# RobotCtrl_Base_Func.net
KiCad netlist of a schematic drawn in Altium Designer
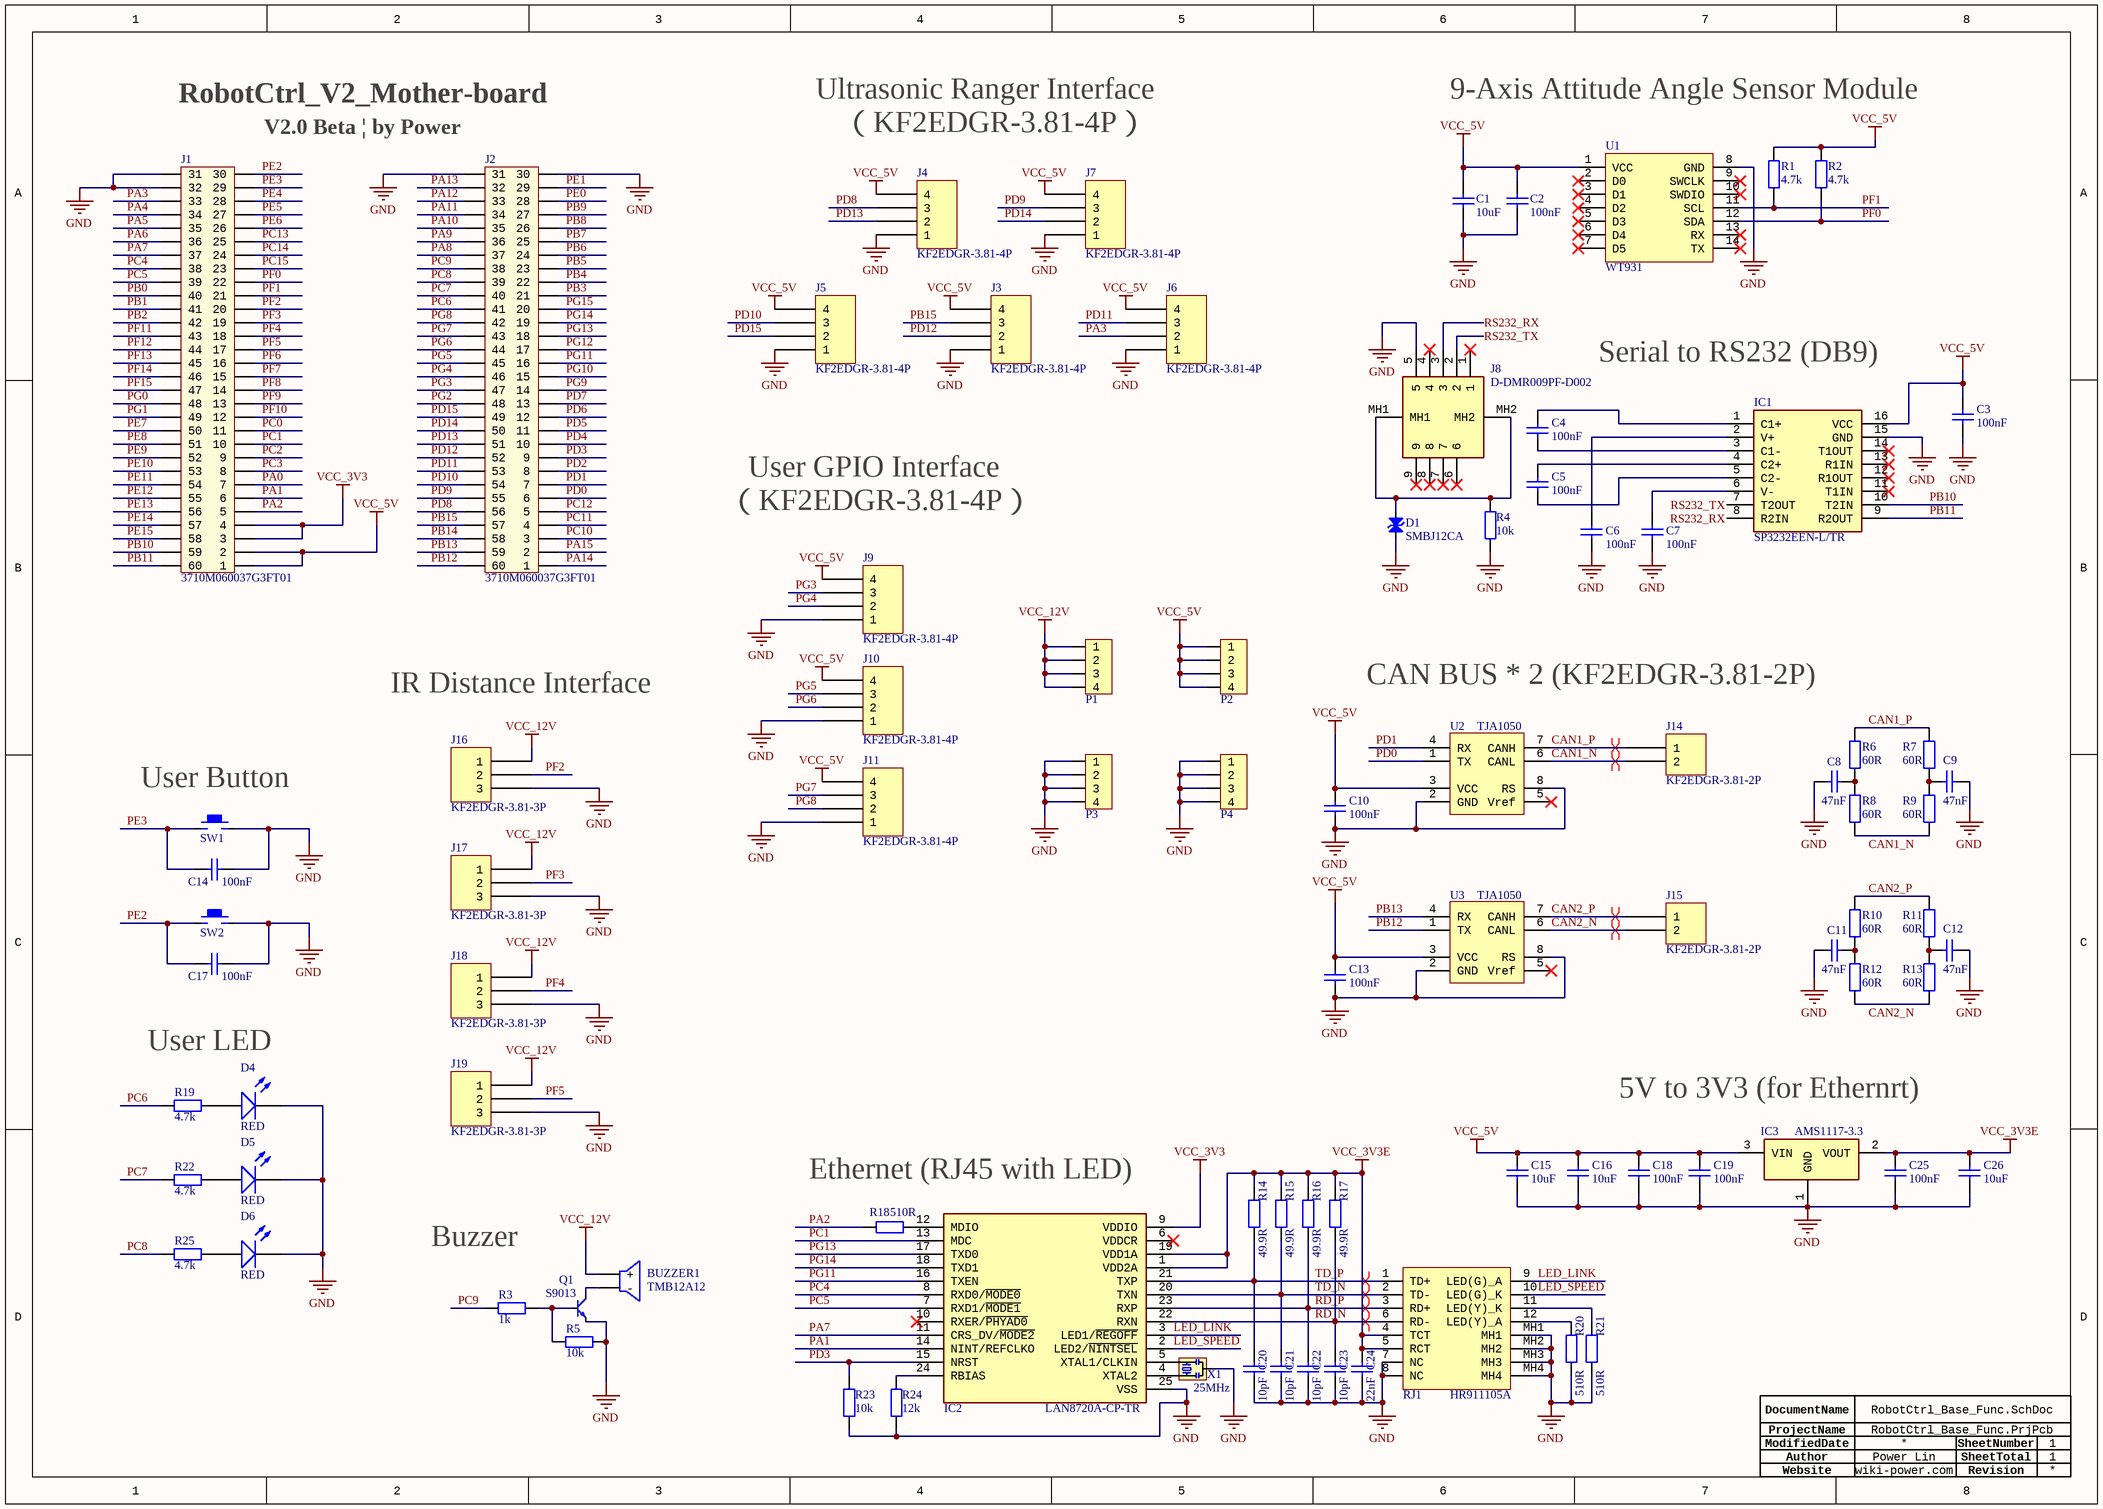
[diagram p0: RobotCtrl_Base_Func.SchDoc]

(export (version "E")
  (design (tool "Eeschema 10.0.6"))
  (components
    (comp (ref "BUZZER1")
      (value "TMB12A12")
      (footprint "DIP,P=7.6mm")
      (description "TMB12A12 有源蜂鸣器")
      (libsource (lib "Power_Lib_Altium") (part "BUZZER"))
    )
    (comp (ref "C1")
      (value "10uF")
      (footprint "CAP-0603")
      (description "贴片电容")
      (libsource (lib "Power_Lib_Altium") (part "CAP"))
    )
    (comp (ref "C2")
      (value "100nF")
      (footprint "CAP-0603")
      (description "贴片电容")
      (libsource (lib "Power_Lib_Altium") (part "CAP"))
    )
    (comp (ref "C3")
      (value "100nF")
      (footprint "CAP-0603")
      (description "贴片电容")
      (libsource (lib "Power_Lib_Altium") (part "CAP"))
    )
    (comp (ref "C4")
      (value "100nF")
      (footprint "CAP-0603")
      (description "贴片电容")
      (libsource (lib "Power_Lib_Altium") (part "CAP"))
    )
    (comp (ref "C5")
      (value "100nF")
      (footprint "CAP-0603")
      (description "贴片电容")
      (libsource (lib "Power_Lib_Altium") (part "CAP"))
    )
    (comp (ref "C6")
      (value "100nF")
      (footprint "CAP-0603")
      (description "贴片电容")
      (libsource (lib "Power_Lib_Altium") (part "CAP"))
    )
    (comp (ref "C7")
      (value "100nF")
      (footprint "CAP-0603")
      (description "贴片电容")
      (libsource (lib "Power_Lib_Altium") (part "CAP"))
    )
    (comp (ref "C8")
      (value "47nF")
      (footprint "CAP-0603")
      (description "贴片电容")
      (libsource (lib "Power_Lib_Altium") (part "CAP"))
    )
    (comp (ref "C9")
      (value "47nF")
      (footprint "CAP-0603")
      (description "贴片电容")
      (libsource (lib "Power_Lib_Altium") (part "CAP"))
    )
    (comp (ref "C10")
      (value "100nF")
      (footprint "CAP-0603")
      (description "贴片电容")
      (libsource (lib "Power_Lib_Altium") (part "CAP"))
    )
    (comp (ref "C11")
      (value "47nF")
      (footprint "CAP-0603")
      (description "贴片电容")
      (libsource (lib "Power_Lib_Altium") (part "CAP"))
    )
    (comp (ref "C12")
      (value "47nF")
      (footprint "CAP-0603")
      (description "贴片电容")
      (libsource (lib "Power_Lib_Altium") (part "CAP"))
    )
    (comp (ref "C13")
      (value "100nF")
      (footprint "CAP-0603")
      (description "贴片电容")
      (libsource (lib "Power_Lib_Altium") (part "CAP"))
    )
    (comp (ref "C14")
      (value "100nF")
      (footprint "CAP-0603")
      (description "贴片电容")
      (libsource (lib "Power_Lib_Altium") (part "CAP"))
    )
    (comp (ref "C15")
      (value "10uF")
      (footprint "CAP-0603")
      (description "贴片电容")
      (libsource (lib "Power_Lib_Altium") (part "CAP"))
    )
    (comp (ref "C16")
      (value "10uF")
      (footprint "CAP-0603")
      (description "贴片电容")
      (libsource (lib "Power_Lib_Altium") (part "CAP"))
    )
    (comp (ref "C17")
      (value "100nF")
      (footprint "CAP-0603")
      (description "贴片电容")
      (libsource (lib "Power_Lib_Altium") (part "CAP"))
    )
    (comp (ref "C18")
      (value "100nF")
      (footprint "CAP-0603")
      (description "贴片电容")
      (libsource (lib "Power_Lib_Altium") (part "CAP"))
    )
    (comp (ref "C19")
      (value "100nF")
      (footprint "CAP-0603")
      (description "贴片电容")
      (libsource (lib "Power_Lib_Altium") (part "CAP"))
    )
    (comp (ref "C20")
      (value "10pF")
      (footprint "CAP-0603")
      (description "贴片电容")
      (libsource (lib "Power_Lib_Altium") (part "CAP"))
    )
    (comp (ref "C21")
      (value "10pF")
      (footprint "CAP-0603")
      (description "贴片电容")
      (libsource (lib "Power_Lib_Altium") (part "CAP"))
    )
    (comp (ref "C22")
      (value "10pF")
      (footprint "CAP-0603")
      (description "贴片电容")
      (libsource (lib "Power_Lib_Altium") (part "CAP"))
    )
    (comp (ref "C23")
      (value "10pF")
      (footprint "CAP-0603")
      (description "贴片电容")
      (libsource (lib "Power_Lib_Altium") (part "CAP"))
    )
    (comp (ref "C24")
      (value "22nF")
      (footprint "CAP-0603")
      (description "贴片电容")
      (libsource (lib "Power_Lib_Altium") (part "CAP"))
    )
    (comp (ref "C25")
      (value "100nF")
      (footprint "CAP-0603")
      (description "贴片电容")
      (libsource (lib "Power_Lib_Altium") (part "CAP"))
    )
    (comp (ref "C26")
      (value "10uF")
      (footprint "CAP-0603")
      (description "贴片电容")
      (libsource (lib "Power_Lib_Altium") (part "CAP"))
    )
    (comp (ref "D1")
      (value "SMBJ12CA")
      (footprint "DO-214AA/SMB")
      (libsource (lib "Power_Lib_Altium") (part "TVS_C"))
    )
    (comp (ref "D4")
      (value "RED")
      (footprint "LED-0603")
      (description "发光二极管")
      (libsource (lib "Power_Lib_Altium") (part "LED"))
    )
    (comp (ref "D5")
      (value "RED")
      (footprint "LED-0603")
      (description "发光二极管")
      (libsource (lib "Power_Lib_Altium") (part "LED"))
    )
    (comp (ref "D6")
      (value "RED")
      (footprint "LED-0603")
      (description "发光二极管")
      (libsource (lib "Power_Lib_Altium") (part "LED"))
    )
    (comp (ref "IC1")
      (value "SP3232EEN-L/TR")
      (footprint "SOIC-16_150mil")
      (description "RS232 芯片")
      (fields (field (name "MOUSER PART NUMBER") "701-SP3232EEN-L/TR"))
      (libsource (lib "Power_Lib_Altium") (part "SP3232EEN"))
    )
    (comp (ref "IC2")
      (value "LAN8720A-CP-TR")
      (footprint "QFN-24-4x4")
      (description "Integrated Circuit")
      (fields (field (name "MOUSER PART NUMBER") "886-LAN8720A-CP-TR"))
      (libsource (lib "Power_Lib_Altium") (part "LAN8720A-CP-TR"))
    )
    (comp (ref "IC3")
      (value "AMS1117-3.3")
      (footprint "SOT-223")
      (description "AMS1117-3.3 1.0A")
      (fields (field (name "MANUFACTURER_PART_NUMBER") "SI2302DS") (field (name "RS PART NUMBER") "7983053P"))
      (libsource (lib "Power_Lib_Altium") (part "AMS1117"))
    )
    (comp (ref "J1")
      (value "3710M060037G3FT01")
      (footprint "3710M060037G3FT01")
      (description "B2B Connector")
      (libsource (lib "Power_Lib_Altium") (part "3710M/F"))
    )
    (comp (ref "J2")
      (value "3710M060037G3FT01")
      (footprint "3710M060037G3FT01")
      (description "B2B Connector")
      (libsource (lib "Power_Lib_Altium") (part "3710M/F"))
    )
    (comp (ref "J3")
      (value "KF2EDGR-3.81-4P")
      (footprint "FCI 06-381-4PIN")
      (description "TERM BLOCK HDR 4POS 90DEG 3.81MM")
      (fields (field (name "PART NUMBER") "OQ0432510000G") (field (name "MANUFACTURER") "Amphenol Anytek"))
      (libsource (lib "Power_Lib_Altium") (part "KF2EDGR-3.81-4P"))
    )
    (comp (ref "J4")
      (value "KF2EDGR-3.81-4P")
      (footprint "FCI 06-381-4PIN")
      (description "TERM BLOCK HDR 4POS 90DEG 3.81MM")
      (fields (field (name "PART NUMBER") "OQ0432510000G") (field (name "MANUFACTURER") "Amphenol Anytek"))
      (libsource (lib "Power_Lib_Altium") (part "KF2EDGR-3.81-4P"))
    )
    (comp (ref "J5")
      (value "KF2EDGR-3.81-4P")
      (footprint "FCI 06-381-4PIN")
      (description "TERM BLOCK HDR 4POS 90DEG 3.81MM")
      (fields (field (name "PART NUMBER") "OQ0432510000G") (field (name "MANUFACTURER") "Amphenol Anytek"))
      (libsource (lib "Power_Lib_Altium") (part "KF2EDGR-3.81-4P"))
    )
    (comp (ref "J6")
      (value "KF2EDGR-3.81-4P")
      (footprint "FCI 06-381-4PIN")
      (description "TERM BLOCK HDR 4POS 90DEG 3.81MM")
      (fields (field (name "PART NUMBER") "OQ0432510000G") (field (name "MANUFACTURER") "Amphenol Anytek"))
      (libsource (lib "Power_Lib_Altium") (part "KF2EDGR-3.81-4P"))
    )
    (comp (ref "J7")
      (value "KF2EDGR-3.81-4P")
      (footprint "FCI 06-381-4PIN")
      (description "TERM BLOCK HDR 4POS 90DEG 3.81MM")
      (fields (field (name "PART NUMBER") "OQ0432510000G") (field (name "MANUFACTURER") "Amphenol Anytek"))
      (libsource (lib "Power_Lib_Altium") (part "KF2EDGR-3.81-4P"))
    )
    (comp (ref "J8")
      (value "D-DMR009PF-D002")
      (footprint "Through Hole,P=2.77mm")
      (description "D-Sub 连接器")
      (fields
        (field (name "MANUFACTURER_PART_NUMBER") "5747844-5")
        (field (name "MOUSER PART NUMBER") "571-5747844-5")
      )
      (libsource (lib "Power_Lib_Altium") (part "DB9"))
    )
    (comp (ref "J9")
      (value "KF2EDGR-3.81-4P")
      (footprint "FCI 06-381-4PIN")
      (description "TERM BLOCK HDR 4POS 90DEG 3.81MM")
      (fields (field (name "PART NUMBER") "OQ0432510000G") (field (name "MANUFACTURER") "Amphenol Anytek"))
      (libsource (lib "Power_Lib_Altium") (part "KF2EDGR-3.81-4P"))
    )
    (comp (ref "J10")
      (value "KF2EDGR-3.81-4P")
      (footprint "FCI 06-381-4PIN")
      (description "TERM BLOCK HDR 4POS 90DEG 3.81MM")
      (fields (field (name "PART NUMBER") "OQ0432510000G") (field (name "MANUFACTURER") "Amphenol Anytek"))
      (libsource (lib "Power_Lib_Altium") (part "KF2EDGR-3.81-4P"))
    )
    (comp (ref "J11")
      (value "KF2EDGR-3.81-4P")
      (footprint "FCI 06-381-4PIN")
      (description "TERM BLOCK HDR 4POS 90DEG 3.81MM")
      (fields (field (name "PART NUMBER") "OQ0432510000G") (field (name "MANUFACTURER") "Amphenol Anytek"))
      (libsource (lib "Power_Lib_Altium") (part "KF2EDGR-3.81-4P"))
    )
    (comp (ref "J14")
      (value "KF2EDGR-3.81-2P")
      (footprint "FCI 06-381-2PIN")
      (description "TERM BLOCK HDR 2POS 90DEG 3.81MM")
      (fields (field (name "PART NUMBER") "OQ0232510000G") (field (name "MANUFACTURER") "Amphenol Anytek"))
      (libsource (lib "Power_Lib_Altium") (part "KF2EDGR-3.81-2P"))
    )
    (comp (ref "J15")
      (value "KF2EDGR-3.81-2P")
      (footprint "FCI 06-381-2PIN")
      (description "TERM BLOCK HDR 2POS 90DEG 3.81MM")
      (fields (field (name "PART NUMBER") "OQ0232510000G") (field (name "MANUFACTURER") "Amphenol Anytek"))
      (libsource (lib "Power_Lib_Altium") (part "KF2EDGR-3.81-2P"))
    )
    (comp (ref "J16")
      (value "KF2EDGR-3.81-3P")
      (footprint "FCI 06-381-3PIN")
      (description "TERM BLOCK HDR 3POS 90DEG 3.81MM")
      (fields (field (name "MANUFACTURER") "Amphenol Anytek") (field (name "PART NUMBER") "OQ0332510000G"))
      (libsource (lib "Power_Lib_Altium") (part "KF2EDGR-3.81-3P"))
    )
    (comp (ref "J17")
      (value "KF2EDGR-3.81-3P")
      (footprint "FCI 06-381-3PIN")
      (description "TERM BLOCK HDR 3POS 90DEG 3.81MM")
      (fields (field (name "MANUFACTURER") "Amphenol Anytek") (field (name "PART NUMBER") "OQ0332510000G"))
      (libsource (lib "Power_Lib_Altium") (part "KF2EDGR-3.81-3P"))
    )
    (comp (ref "J18")
      (value "KF2EDGR-3.81-3P")
      (footprint "FCI 06-381-3PIN")
      (description "TERM BLOCK HDR 3POS 90DEG 3.81MM")
      (fields (field (name "MANUFACTURER") "Amphenol Anytek") (field (name "PART NUMBER") "OQ0332510000G"))
      (libsource (lib "Power_Lib_Altium") (part "KF2EDGR-3.81-3P"))
    )
    (comp (ref "J19")
      (value "KF2EDGR-3.81-3P")
      (footprint "FCI 06-381-3PIN")
      (description "TERM BLOCK HDR 3POS 90DEG 3.81MM")
      (fields (field (name "MANUFACTURER") "Amphenol Anytek") (field (name "PART NUMBER") "OQ0332510000G"))
      (libsource (lib "Power_Lib_Altium") (part "KF2EDGR-3.81-3P"))
    )
    (comp (ref "P1")
      (value "HDR1x4_2.54")
      (footprint "HDR1X4_2.54")
      (description "Header")
      (libsource (lib "Power_Lib_Altium") (part "HDR1x4_2.54"))
    )
    (comp (ref "P2")
      (value "HDR1x4_2.54")
      (footprint "HDR1X4_2.54")
      (description "Header")
      (libsource (lib "Power_Lib_Altium") (part "HDR1x4_2.54"))
    )
    (comp (ref "P3")
      (value "HDR1x4_2.54")
      (footprint "HDR1X4_2.54")
      (description "Header")
      (libsource (lib "Power_Lib_Altium") (part "HDR1x4_2.54"))
    )
    (comp (ref "P4")
      (value "HDR1x4_2.54")
      (footprint "HDR1X4_2.54")
      (description "Header")
      (libsource (lib "Power_Lib_Altium") (part "HDR1x4_2.54"))
    )
    (comp (ref "Q1")
      (value "S9013")
      (footprint "SOT-23-3")
      (libsource (lib "Power_Lib_Altium") (part "BJT_NPN"))
    )
    (comp (ref "R1")
      (value "4.7k")
      (footprint "R-0603")
      (description "贴片电阻")
      (libsource (lib "Power_Lib_Altium") (part "RES"))
    )
    (comp (ref "R2")
      (value "4.7k")
      (footprint "R-0603")
      (description "贴片电阻")
      (libsource (lib "Power_Lib_Altium") (part "RES"))
    )
    (comp (ref "R3")
      (value "1k")
      (footprint "R-0603")
      (description "贴片电阻")
      (libsource (lib "") (part "RES_3"))
    )
    (comp (ref "R4")
      (value "10k")
      (footprint "R-0603")
      (description "贴片电阻")
      (libsource (lib "Power_Lib_Altium") (part "RES"))
    )
    (comp (ref "R5")
      (value "10k")
      (footprint "R-0603")
      (description "贴片电阻")
      (libsource (lib "") (part "RES_2"))
    )
    (comp (ref "R6")
      (value "60R")
      (footprint "R-0603")
      (description "贴片电阻")
      (libsource (lib "") (part "RES_1"))
    )
    (comp (ref "R7")
      (value "60R")
      (footprint "R-0603")
      (description "贴片电阻")
      (libsource (lib "Power_Lib_Altium") (part "RES"))
    )
    (comp (ref "R8")
      (value "60R")
      (footprint "R-0603")
      (description "贴片电阻")
      (libsource (lib "") (part "RES_1"))
    )
    (comp (ref "R9")
      (value "60R")
      (footprint "R-0603")
      (description "贴片电阻")
      (libsource (lib "Power_Lib_Altium") (part "RES"))
    )
    (comp (ref "R10")
      (value "60R")
      (footprint "R-0603")
      (description "贴片电阻")
      (libsource (lib "") (part "RES_1"))
    )
    (comp (ref "R11")
      (value "60R")
      (footprint "R-0603")
      (description "贴片电阻")
      (libsource (lib "Power_Lib_Altium") (part "RES"))
    )
    (comp (ref "R12")
      (value "60R")
      (footprint "R-0603")
      (description "贴片电阻")
      (libsource (lib "") (part "RES_1"))
    )
    (comp (ref "R13")
      (value "60R")
      (footprint "R-0603")
      (description "贴片电阻")
      (libsource (lib "Power_Lib_Altium") (part "RES"))
    )
    (comp (ref "R14")
      (value "49.9R")
      (footprint "R-0603")
      (description "贴片电阻")
      (libsource (lib "Power_Lib_Altium") (part "RES"))
    )
    (comp (ref "R15")
      (value "49.9R")
      (footprint "R-0603")
      (description "贴片电阻")
      (libsource (lib "Power_Lib_Altium") (part "RES"))
    )
    (comp (ref "R16")
      (value "49.9R")
      (footprint "R-0603")
      (description "贴片电阻")
      (libsource (lib "Power_Lib_Altium") (part "RES"))
    )
    (comp (ref "R17")
      (value "49.9R")
      (footprint "R-0603")
      (description "贴片电阻")
      (libsource (lib "Power_Lib_Altium") (part "RES"))
    )
    (comp (ref "R18")
      (value "510R")
      (footprint "R-0603")
      (description "贴片电阻")
      (libsource (lib "") (part "RES_2"))
    )
    (comp (ref "R19")
      (value "4.7k")
      (footprint "R-0603")
      (description "贴片电阻")
      (libsource (lib "") (part "RES_2"))
    )
    (comp (ref "R20")
      (value "510R")
      (footprint "R-0603")
      (description "贴片电阻")
      (libsource (lib "Power_Lib_Altium") (part "RES"))
    )
    (comp (ref "R21")
      (value "510R")
      (footprint "R-0603")
      (description "贴片电阻")
      (libsource (lib "Power_Lib_Altium") (part "RES"))
    )
    (comp (ref "R22")
      (value "4.7k")
      (footprint "R-0603")
      (description "贴片电阻")
      (libsource (lib "") (part "RES_2"))
    )
    (comp (ref "R23")
      (value "10k")
      (footprint "R-0603")
      (description "贴片电阻")
      (libsource (lib "") (part "RES_1"))
    )
    (comp (ref "R24")
      (value "12k")
      (footprint "R-0603")
      (description "贴片电阻")
      (libsource (lib "") (part "RES_1"))
    )
    (comp (ref "R25")
      (value "4.7k")
      (footprint "R-0603")
      (description "贴片电阻")
      (libsource (lib "") (part "RES_2"))
    )
    (comp (ref "RJ1")
      (value "HR911105A")
      (footprint "HR911105A")
      (description "内置变压器的RJ45")
      (libsource (lib "Power_Lib_Altium") (part "RJ45_LED"))
    )
    (comp (ref "SW1")
      (value "KEY")
      (footprint "KEY-4P-4.2*3.4*2.5")
      (description "按键开关")
      (libsource (lib "Power_Lib_Altium") (part "KEY"))
    )
    (comp (ref "SW2")
      (value "KEY")
      (footprint "KEY-4P-4.2*3.4*2.5")
      (description "按键开关")
      (libsource (lib "Power_Lib_Altium") (part "KEY"))
    )
    (comp (ref "U1")
      (value "WT931")
      (footprint "WT931")
      (description "陀螺仪模组")
      (libsource (lib "Power_Lib_Altium") (part "WT931"))
    )
    (comp (ref "U2")
      (value "TJA1050")
      (footprint "SOIC_8")
      (description "CAN 控制器（5V）")
      (libsource (lib "Power_Lib_Altium") (part "TJA1050"))
    )
    (comp (ref "U3")
      (value "TJA1050")
      (footprint "SOIC_8")
      (description "CAN 控制器（5V）")
      (libsource (lib "Power_Lib_Altium") (part "TJA1050"))
    )
    (comp (ref "X1")
      (value "25MHz")
      (footprint "SMD3213-3P")
      (description "CSTCE25M00G51-R0")
      (libsource (lib "Power_Lib_Altium") (part "XTAL"))
    )
  )
  (nets
    (net (code "1") (name "/CAN1_N") (class "Default")
      (node (ref "J14") (pin "2") (pinfunction "2_2") (pintype "passive"))
      (node (ref "R8") (pin "2") (pinfunction "2_2") (pintype "passive"))
      (node (ref "R9") (pin "1") (pinfunction "1_1") (pintype "passive"))
      (node (ref "U2") (pin "6") (pinfunction "CANL_6") (pintype "passive"))
    )
    (net (code "2") (name "/CAN1_P") (class "Default")
      (node (ref "J14") (pin "1") (pinfunction "1_1") (pintype "passive"))
      (node (ref "R6") (pin "1") (pinfunction "1_1") (pintype "passive"))
      (node (ref "R7") (pin "2") (pinfunction "2_2") (pintype "passive"))
      (node (ref "U2") (pin "7") (pinfunction "CANH_7") (pintype "passive"))
    )
    (net (code "3") (name "/CAN2_N") (class "Default")
      (node (ref "J15") (pin "2") (pinfunction "2_2") (pintype "passive"))
      (node (ref "R12") (pin "2") (pinfunction "2_2") (pintype "passive"))
      (node (ref "R13") (pin "1") (pinfunction "1_1") (pintype "passive"))
      (node (ref "U3") (pin "6") (pinfunction "CANL_6") (pintype "passive"))
    )
    (net (code "4") (name "/CAN2_P") (class "Default")
      (node (ref "J15") (pin "1") (pinfunction "1_1") (pintype "passive"))
      (node (ref "R10") (pin "1") (pinfunction "1_1") (pintype "passive"))
      (node (ref "R11") (pin "2") (pinfunction "2_2") (pintype "passive"))
      (node (ref "U3") (pin "7") (pinfunction "CANH_7") (pintype "passive"))
    )
    (net (code "5") (name "/LED_LINK") (class "Default")
      (node (ref "IC2") (pin "3") (pinfunction "LED1/~{REGOFF}_3") (pintype "passive"))
      (node (ref "RJ1") (pin "9") (pinfunction "LED(G)_A_9") (pintype "passive"))
    )
    (net (code "6") (name "/LED_SPEED") (class "Default")
      (node (ref "IC2") (pin "2") (pinfunction "LED2/~{NINTSEL}_2") (pintype "passive"))
      (node (ref "RJ1") (pin "10") (pinfunction "LED(G)_K_10") (pintype "passive"))
    )
    (net (code "7") (name "/PA0") (class "Default")
      (node (ref "J1") (pin "7") (pinfunction "7_7") (pintype "passive"))
    )
    (net (code "8") (name "/PA1") (class "Default")
      (node (ref "IC2") (pin "14") (pinfunction "NINT/REFCLKO_14") (pintype "passive"))
      (node (ref "J1") (pin "6") (pinfunction "6_6") (pintype "passive"))
    )
    (net (code "9") (name "/PA2") (class "Default")
      (node (ref "J1") (pin "5") (pinfunction "5_5") (pintype "passive"))
      (node (ref "R18") (pin "2") (pinfunction "2_2") (pintype "passive"))
    )
    (net (code "10") (name "/PA3") (class "Default")
      (node (ref "J1") (pin "33") (pinfunction "33_33") (pintype "passive"))
      (node (ref "J6") (pin "2") (pinfunction "2_2") (pintype "passive"))
    )
    (net (code "11") (name "/PA4") (class "Default")
      (node (ref "J1") (pin "34") (pinfunction "34_34") (pintype "passive"))
    )
    (net (code "12") (name "/PA5") (class "Default")
      (node (ref "J1") (pin "35") (pinfunction "35_35") (pintype "passive"))
    )
    (net (code "13") (name "/PA6") (class "Default")
      (node (ref "J1") (pin "36") (pinfunction "36_36") (pintype "passive"))
    )
    (net (code "14") (name "/PA7") (class "Default")
      (node (ref "IC2") (pin "11") (pinfunction "CRS_DV/~{MODE2}_11") (pintype "passive"))
      (node (ref "J1") (pin "37") (pinfunction "37_37") (pintype "passive"))
    )
    (net (code "15") (name "/PA8") (class "Default")
      (node (ref "J2") (pin "37") (pinfunction "37_37") (pintype "passive"))
    )
    (net (code "16") (name "/PA9") (class "Default")
      (node (ref "J2") (pin "36") (pinfunction "36_36") (pintype "passive"))
    )
    (net (code "17") (name "/PA10") (class "Default")
      (node (ref "J2") (pin "35") (pinfunction "35_35") (pintype "passive"))
    )
    (net (code "18") (name "/PA11") (class "Default")
      (node (ref "J2") (pin "34") (pinfunction "34_34") (pintype "passive"))
    )
    (net (code "19") (name "/PA12") (class "Default")
      (node (ref "J2") (pin "33") (pinfunction "33_33") (pintype "passive"))
    )
    (net (code "20") (name "/PA13") (class "Default")
      (node (ref "J2") (pin "32") (pinfunction "32_32") (pintype "passive"))
    )
    (net (code "21") (name "/PA14") (class "Default")
      (node (ref "J2") (pin "1") (pinfunction "1_1") (pintype "passive"))
    )
    (net (code "22") (name "/PA15") (class "Default")
      (node (ref "J2") (pin "2") (pinfunction "2_2") (pintype "passive"))
    )
    (net (code "23") (name "/PB0") (class "Default")
      (node (ref "J1") (pin "40") (pinfunction "40_40") (pintype "passive"))
    )
    (net (code "24") (name "/PB1") (class "Default")
      (node (ref "J1") (pin "41") (pinfunction "41_41") (pintype "passive"))
    )
    (net (code "25") (name "/PB2") (class "Default")
      (node (ref "J1") (pin "42") (pinfunction "42_42") (pintype "passive"))
    )
    (net (code "26") (name "/PB3") (class "Default")
      (node (ref "J2") (pin "21") (pinfunction "21_21") (pintype "passive"))
    )
    (net (code "27") (name "/PB4") (class "Default")
      (node (ref "J2") (pin "22") (pinfunction "22_22") (pintype "passive"))
    )
    (net (code "28") (name "/PB5") (class "Default")
      (node (ref "J2") (pin "23") (pinfunction "23_23") (pintype "passive"))
    )
    (net (code "29") (name "/PB6") (class "Default")
      (node (ref "J2") (pin "24") (pinfunction "24_24") (pintype "passive"))
    )
    (net (code "30") (name "/PB7") (class "Default")
      (node (ref "J2") (pin "25") (pinfunction "25_25") (pintype "passive"))
    )
    (net (code "31") (name "/PB8") (class "Default")
      (node (ref "J2") (pin "26") (pinfunction "26_26") (pintype "passive"))
    )
    (net (code "32") (name "/PB9") (class "Default")
      (node (ref "J2") (pin "27") (pinfunction "27_27") (pintype "passive"))
    )
    (net (code "33") (name "/PB10") (class "Default")
      (node (ref "IC1") (pin "10") (pinfunction "T2IN_10") (pintype "passive"))
      (node (ref "J1") (pin "59") (pinfunction "59_59") (pintype "passive"))
    )
    (net (code "34") (name "/PB11") (class "Default")
      (node (ref "IC1") (pin "9") (pinfunction "R2OUT_9") (pintype "passive"))
      (node (ref "J1") (pin "60") (pinfunction "60_60") (pintype "passive"))
    )
    (net (code "35") (name "/PB12") (class "Default")
      (node (ref "J2") (pin "60") (pinfunction "60_60") (pintype "passive"))
      (node (ref "U3") (pin "1") (pinfunction "TX_1") (pintype "passive"))
    )
    (net (code "36") (name "/PB13") (class "Default")
      (node (ref "J2") (pin "59") (pinfunction "59_59") (pintype "passive"))
      (node (ref "U3") (pin "4") (pinfunction "RX_4") (pintype "passive"))
    )
    (net (code "37") (name "/PB14") (class "Default")
      (node (ref "J2") (pin "58") (pinfunction "58_58") (pintype "passive"))
    )
    (net (code "38") (name "/PB15") (class "Default")
      (node (ref "J2") (pin "57") (pinfunction "57_57") (pintype "passive"))
      (node (ref "J3") (pin "3") (pinfunction "3_3") (pintype "passive"))
    )
    (net (code "39") (name "/PC0") (class "Default")
      (node (ref "J1") (pin "11") (pinfunction "11_11") (pintype "passive"))
    )
    (net (code "40") (name "/PC1") (class "Default")
      (node (ref "IC2") (pin "13") (pinfunction "MDC_13") (pintype "passive"))
      (node (ref "J1") (pin "10") (pinfunction "10_10") (pintype "passive"))
    )
    (net (code "41") (name "/PC2") (class "Default")
      (node (ref "J1") (pin "9") (pinfunction "9_9") (pintype "passive"))
    )
    (net (code "42") (name "/PC3") (class "Default")
      (node (ref "J1") (pin "8") (pinfunction "8_8") (pintype "passive"))
    )
    (net (code "43") (name "/PC4") (class "Default")
      (node (ref "IC2") (pin "8") (pinfunction "RXD0/~{MODE0}_8") (pintype "passive"))
      (node (ref "J1") (pin "38") (pinfunction "38_38") (pintype "passive"))
    )
    (net (code "44") (name "/PC5") (class "Default")
      (node (ref "IC2") (pin "7") (pinfunction "RXD1/~{MODE1}_7") (pintype "passive"))
      (node (ref "J1") (pin "39") (pinfunction "39_39") (pintype "passive"))
    )
    (net (code "45") (name "/PC6") (class "Default")
      (node (ref "J2") (pin "41") (pinfunction "41_41") (pintype "passive"))
      (node (ref "R19") (pin "2") (pinfunction "2_2") (pintype "passive"))
    )
    (net (code "46") (name "/PC7") (class "Default")
      (node (ref "J2") (pin "40") (pinfunction "40_40") (pintype "passive"))
      (node (ref "R22") (pin "2") (pinfunction "2_2") (pintype "passive"))
    )
    (net (code "47") (name "/PC8") (class "Default")
      (node (ref "J2") (pin "39") (pinfunction "39_39") (pintype "passive"))
      (node (ref "R25") (pin "2") (pinfunction "2_2") (pintype "passive"))
    )
    (net (code "48") (name "/PC9") (class "Default")
      (node (ref "J2") (pin "38") (pinfunction "38_38") (pintype "passive"))
      (node (ref "R3") (pin "1") (pinfunction "1_1") (pintype "passive"))
    )
    (net (code "49") (name "/PC10") (class "Default")
      (node (ref "J2") (pin "3") (pinfunction "3_3") (pintype "passive"))
    )
    (net (code "50") (name "/PC11") (class "Default")
      (node (ref "J2") (pin "4") (pinfunction "4_4") (pintype "passive"))
    )
    (net (code "51") (name "/PC12") (class "Default")
      (node (ref "J2") (pin "5") (pinfunction "5_5") (pintype "passive"))
    )
    (net (code "52") (name "/PC13") (class "Default")
      (node (ref "J1") (pin "25") (pinfunction "25_25") (pintype "passive"))
    )
    (net (code "53") (name "/PC14") (class "Default")
      (node (ref "J1") (pin "24") (pinfunction "24_24") (pintype "passive"))
    )
    (net (code "54") (name "/PC15") (class "Default")
      (node (ref "J1") (pin "23") (pinfunction "23_23") (pintype "passive"))
    )
    (net (code "55") (name "/PD0") (class "Default")
      (node (ref "J2") (pin "6") (pinfunction "6_6") (pintype "passive"))
      (node (ref "U2") (pin "1") (pinfunction "TX_1") (pintype "passive"))
    )
    (net (code "56") (name "/PD1") (class "Default")
      (node (ref "J2") (pin "7") (pinfunction "7_7") (pintype "passive"))
      (node (ref "U2") (pin "4") (pinfunction "RX_4") (pintype "passive"))
    )
    (net (code "57") (name "/PD2") (class "Default")
      (node (ref "J2") (pin "8") (pinfunction "8_8") (pintype "passive"))
    )
    (net (code "58") (name "/PD3") (class "Default")
      (node (ref "IC2") (pin "15") (pinfunction "NRST_15") (pintype "passive"))
      (node (ref "J2") (pin "9") (pinfunction "9_9") (pintype "passive"))
      (node (ref "R23") (pin "1") (pinfunction "1_1") (pintype "passive"))
    )
    (net (code "59") (name "/PD4") (class "Default")
      (node (ref "J2") (pin "10") (pinfunction "10_10") (pintype "passive"))
    )
    (net (code "60") (name "/PD5") (class "Default")
      (node (ref "J2") (pin "11") (pinfunction "11_11") (pintype "passive"))
    )
    (net (code "61") (name "/PD6") (class "Default")
      (node (ref "J2") (pin "12") (pinfunction "12_12") (pintype "passive"))
    )
    (net (code "62") (name "/PD7") (class "Default")
      (node (ref "J2") (pin "13") (pinfunction "13_13") (pintype "passive"))
    )
    (net (code "63") (name "/PD8") (class "Default")
      (node (ref "J2") (pin "56") (pinfunction "56_56") (pintype "passive"))
      (node (ref "J4") (pin "3") (pinfunction "3_3") (pintype "passive"))
    )
    (net (code "64") (name "/PD9") (class "Default")
      (node (ref "J2") (pin "55") (pinfunction "55_55") (pintype "passive"))
      (node (ref "J7") (pin "3") (pinfunction "3_3") (pintype "passive"))
    )
    (net (code "65") (name "/PD10") (class "Default")
      (node (ref "J2") (pin "54") (pinfunction "54_54") (pintype "passive"))
      (node (ref "J5") (pin "3") (pinfunction "3_3") (pintype "passive"))
    )
    (net (code "66") (name "/PD11") (class "Default")
      (node (ref "J2") (pin "53") (pinfunction "53_53") (pintype "passive"))
      (node (ref "J6") (pin "3") (pinfunction "3_3") (pintype "passive"))
    )
    (net (code "67") (name "/PD12") (class "Default")
      (node (ref "J2") (pin "52") (pinfunction "52_52") (pintype "passive"))
      (node (ref "J3") (pin "2") (pinfunction "2_2") (pintype "passive"))
    )
    (net (code "68") (name "/PD13") (class "Default")
      (node (ref "J2") (pin "51") (pinfunction "51_51") (pintype "passive"))
      (node (ref "J4") (pin "2") (pinfunction "2_2") (pintype "passive"))
    )
    (net (code "69") (name "/PD14") (class "Default")
      (node (ref "J2") (pin "50") (pinfunction "50_50") (pintype "passive"))
      (node (ref "J7") (pin "2") (pinfunction "2_2") (pintype "passive"))
    )
    (net (code "70") (name "/PD15") (class "Default")
      (node (ref "J2") (pin "49") (pinfunction "49_49") (pintype "passive"))
      (node (ref "J5") (pin "2") (pinfunction "2_2") (pintype "passive"))
    )
    (net (code "71") (name "/PE0") (class "Default")
      (node (ref "J2") (pin "28") (pinfunction "28_28") (pintype "passive"))
    )
    (net (code "72") (name "/PE1") (class "Default")
      (node (ref "J2") (pin "29") (pinfunction "29_29") (pintype "passive"))
    )
    (net (code "73") (name "/PE2") (class "Default")
      (node (ref "C17") (pin "2") (pinfunction "2_2") (pintype "passive"))
      (node (ref "J1") (pin "30") (pinfunction "30_30") (pintype "passive"))
      (node (ref "SW2") (pin "1") (pinfunction "1_1") (pintype "passive"))
    )
    (net (code "74") (name "/PE3") (class "Default")
      (node (ref "C14") (pin "2") (pinfunction "2_2") (pintype "passive"))
      (node (ref "J1") (pin "29") (pinfunction "29_29") (pintype "passive"))
      (node (ref "SW1") (pin "1") (pinfunction "1_1") (pintype "passive"))
    )
    (net (code "75") (name "/PE4") (class "Default")
      (node (ref "J1") (pin "28") (pinfunction "28_28") (pintype "passive"))
    )
    (net (code "76") (name "/PE5") (class "Default")
      (node (ref "J1") (pin "27") (pinfunction "27_27") (pintype "passive"))
    )
    (net (code "77") (name "/PE6") (class "Default")
      (node (ref "J1") (pin "26") (pinfunction "26_26") (pintype "passive"))
    )
    (net (code "78") (name "/PE7") (class "Default")
      (node (ref "J1") (pin "50") (pinfunction "50_50") (pintype "passive"))
    )
    (net (code "79") (name "/PE8") (class "Default")
      (node (ref "J1") (pin "51") (pinfunction "51_51") (pintype "passive"))
    )
    (net (code "80") (name "/PE9") (class "Default")
      (node (ref "J1") (pin "52") (pinfunction "52_52") (pintype "passive"))
    )
    (net (code "81") (name "/PE10") (class "Default")
      (node (ref "J1") (pin "53") (pinfunction "53_53") (pintype "passive"))
    )
    (net (code "82") (name "/PE11") (class "Default")
      (node (ref "J1") (pin "54") (pinfunction "54_54") (pintype "passive"))
    )
    (net (code "83") (name "/PE12") (class "Default")
      (node (ref "J1") (pin "55") (pinfunction "55_55") (pintype "passive"))
    )
    (net (code "84") (name "/PE13") (class "Default")
      (node (ref "J1") (pin "56") (pinfunction "56_56") (pintype "passive"))
    )
    (net (code "85") (name "/PE14") (class "Default")
      (node (ref "J1") (pin "57") (pinfunction "57_57") (pintype "passive"))
    )
    (net (code "86") (name "/PE15") (class "Default")
      (node (ref "J1") (pin "58") (pinfunction "58_58") (pintype "passive"))
    )
    (net (code "87") (name "/PF0") (class "Default")
      (node (ref "J1") (pin "22") (pinfunction "22_22") (pintype "passive"))
      (node (ref "R2") (pin "1") (pinfunction "1_1") (pintype "passive"))
      (node (ref "U1") (pin "12") (pinfunction "SDA_12") (pintype "passive"))
    )
    (net (code "88") (name "/PF1") (class "Default")
      (node (ref "J1") (pin "21") (pinfunction "21_21") (pintype "passive"))
      (node (ref "R1") (pin "1") (pinfunction "1_1") (pintype "passive"))
      (node (ref "U1") (pin "11") (pinfunction "SCL_11") (pintype "passive"))
    )
    (net (code "89") (name "/PF2") (class "Default")
      (node (ref "J1") (pin "20") (pinfunction "20_20") (pintype "passive"))
      (node (ref "J16") (pin "2") (pinfunction "2_2") (pintype "passive"))
    )
    (net (code "90") (name "/PF3") (class "Default")
      (node (ref "J1") (pin "19") (pinfunction "19_19") (pintype "passive"))
      (node (ref "J17") (pin "2") (pinfunction "2_2") (pintype "passive"))
    )
    (net (code "91") (name "/PF4") (class "Default")
      (node (ref "J1") (pin "18") (pinfunction "18_18") (pintype "passive"))
      (node (ref "J18") (pin "2") (pinfunction "2_2") (pintype "passive"))
    )
    (net (code "92") (name "/PF5") (class "Default")
      (node (ref "J1") (pin "17") (pinfunction "17_17") (pintype "passive"))
      (node (ref "J19") (pin "2") (pinfunction "2_2") (pintype "passive"))
    )
    (net (code "93") (name "/PF6") (class "Default")
      (node (ref "J1") (pin "16") (pinfunction "16_16") (pintype "passive"))
    )
    (net (code "94") (name "/PF7") (class "Default")
      (node (ref "J1") (pin "15") (pinfunction "15_15") (pintype "passive"))
    )
    (net (code "95") (name "/PF8") (class "Default")
      (node (ref "J1") (pin "14") (pinfunction "14_14") (pintype "passive"))
    )
    (net (code "96") (name "/PF9") (class "Default")
      (node (ref "J1") (pin "13") (pinfunction "13_13") (pintype "passive"))
    )
    (net (code "97") (name "/PF10") (class "Default")
      (node (ref "J1") (pin "12") (pinfunction "12_12") (pintype "passive"))
    )
    (net (code "98") (name "/PF11") (class "Default")
      (node (ref "J1") (pin "43") (pinfunction "43_43") (pintype "passive"))
    )
    (net (code "99") (name "/PF12") (class "Default")
      (node (ref "J1") (pin "44") (pinfunction "44_44") (pintype "passive"))
    )
    (net (code "100") (name "/PF13") (class "Default")
      (node (ref "J1") (pin "45") (pinfunction "45_45") (pintype "passive"))
    )
    (net (code "101") (name "/PF14") (class "Default")
      (node (ref "J1") (pin "46") (pinfunction "46_46") (pintype "passive"))
    )
    (net (code "102") (name "/PF15") (class "Default")
      (node (ref "J1") (pin "47") (pinfunction "47_47") (pintype "passive"))
    )
    (net (code "103") (name "/PG0") (class "Default")
      (node (ref "J1") (pin "48") (pinfunction "48_48") (pintype "passive"))
    )
    (net (code "104") (name "/PG1") (class "Default")
      (node (ref "J1") (pin "49") (pinfunction "49_49") (pintype "passive"))
    )
    (net (code "105") (name "/PG2") (class "Default")
      (node (ref "J2") (pin "48") (pinfunction "48_48") (pintype "passive"))
    )
    (net (code "106") (name "/PG3") (class "Default")
      (node (ref "J2") (pin "47") (pinfunction "47_47") (pintype "passive"))
      (node (ref "J9") (pin "3") (pinfunction "3_3") (pintype "passive"))
    )
    (net (code "107") (name "/PG4") (class "Default")
      (node (ref "J2") (pin "46") (pinfunction "46_46") (pintype "passive"))
      (node (ref "J9") (pin "2") (pinfunction "2_2") (pintype "passive"))
    )
    (net (code "108") (name "/PG5") (class "Default")
      (node (ref "J10") (pin "3") (pinfunction "3_3") (pintype "passive"))
      (node (ref "J2") (pin "45") (pinfunction "45_45") (pintype "passive"))
    )
    (net (code "109") (name "/PG6") (class "Default")
      (node (ref "J10") (pin "2") (pinfunction "2_2") (pintype "passive"))
      (node (ref "J2") (pin "44") (pinfunction "44_44") (pintype "passive"))
    )
    (net (code "110") (name "/PG7") (class "Default")
      (node (ref "J11") (pin "3") (pinfunction "3_3") (pintype "passive"))
      (node (ref "J2") (pin "43") (pinfunction "43_43") (pintype "passive"))
    )
    (net (code "111") (name "/PG8") (class "Default")
      (node (ref "J11") (pin "2") (pinfunction "2_2") (pintype "passive"))
      (node (ref "J2") (pin "42") (pinfunction "42_42") (pintype "passive"))
    )
    (net (code "112") (name "/PG9") (class "Default")
      (node (ref "J2") (pin "14") (pinfunction "14_14") (pintype "passive"))
    )
    (net (code "113") (name "/PG10") (class "Default")
      (node (ref "J2") (pin "15") (pinfunction "15_15") (pintype "passive"))
    )
    (net (code "114") (name "/PG11") (class "Default")
      (node (ref "IC2") (pin "16") (pinfunction "TXEN_16") (pintype "passive"))
      (node (ref "J2") (pin "16") (pinfunction "16_16") (pintype "passive"))
    )
    (net (code "115") (name "/PG12") (class "Default")
      (node (ref "J2") (pin "17") (pinfunction "17_17") (pintype "passive"))
    )
    (net (code "116") (name "/PG13") (class "Default")
      (node (ref "IC2") (pin "17") (pinfunction "TXD0_17") (pintype "passive"))
      (node (ref "J2") (pin "18") (pinfunction "18_18") (pintype "passive"))
    )
    (net (code "117") (name "/PG14") (class "Default")
      (node (ref "IC2") (pin "18") (pinfunction "TXD1_18") (pintype "passive"))
      (node (ref "J2") (pin "19") (pinfunction "19_19") (pintype "passive"))
    )
    (net (code "118") (name "/PG15") (class "Default")
      (node (ref "J2") (pin "20") (pinfunction "20_20") (pintype "passive"))
    )
    (net (code "119") (name "/RD_N") (class "Default")
      (node (ref "C23") (pin "2") (pinfunction "2_2") (pintype "passive"))
      (node (ref "IC2") (pin "22") (pinfunction "RXN_22") (pintype "passive"))
      (node (ref "R17") (pin "1") (pinfunction "1_1") (pintype "passive"))
      (node (ref "RJ1") (pin "6") (pinfunction "RD-_6") (pintype "passive"))
    )
    (net (code "120") (name "/RD_P") (class "Default")
      (node (ref "C22") (pin "2") (pinfunction "2_2") (pintype "passive"))
      (node (ref "IC2") (pin "23") (pinfunction "RXP_23") (pintype "passive"))
      (node (ref "R16") (pin "1") (pinfunction "1_1") (pintype "passive"))
      (node (ref "RJ1") (pin "3") (pinfunction "RD+_3") (pintype "passive"))
    )
    (net (code "121") (name "/RS232_RX") (class "Default")
      (node (ref "IC1") (pin "8") (pinfunction "R2IN_8") (pintype "passive"))
      (node (ref "J8") (pin "3") (pinfunction "3_3") (pintype "passive"))
    )
    (net (code "122") (name "/RS232_TX") (class "Default")
      (node (ref "IC1") (pin "7") (pinfunction "T2OUT_7") (pintype "passive"))
      (node (ref "J8") (pin "2") (pinfunction "2_2") (pintype "passive"))
    )
    (net (code "123") (name "/TD_N") (class "Default")
      (node (ref "C21") (pin "2") (pinfunction "2_2") (pintype "passive"))
      (node (ref "IC2") (pin "20") (pinfunction "TXN_20") (pintype "passive"))
      (node (ref "R15") (pin "1") (pinfunction "1_1") (pintype "passive"))
      (node (ref "RJ1") (pin "2") (pinfunction "TD-_2") (pintype "passive"))
    )
    (net (code "124") (name "/TD_P") (class "Default")
      (node (ref "C20") (pin "2") (pinfunction "2_2") (pintype "passive"))
      (node (ref "IC2") (pin "21") (pinfunction "TXP_21") (pintype "passive"))
      (node (ref "R14") (pin "1") (pinfunction "1_1") (pintype "passive"))
      (node (ref "RJ1") (pin "1") (pinfunction "TD+_1") (pintype "passive"))
    )
    (net (code "125") (name "GND") (class "Default")
      (node (ref "C1") (pin "2") (pinfunction "2_2") (pintype "passive"))
      (node (ref "C10") (pin "1") (pinfunction "1_1") (pintype "passive"))
      (node (ref "C11") (pin "2") (pinfunction "2_2") (pintype "passive"))
      (node (ref "C12") (pin "2") (pinfunction "2_2") (pintype "passive"))
      (node (ref "C13") (pin "1") (pinfunction "1_1") (pintype "passive"))
      (node (ref "C14") (pin "1") (pinfunction "1_1") (pintype "passive"))
      (node (ref "C15") (pin "1") (pinfunction "1_1") (pintype "passive"))
      (node (ref "C16") (pin "1") (pinfunction "1_1") (pintype "passive"))
      (node (ref "C17") (pin "1") (pinfunction "1_1") (pintype "passive"))
      (node (ref "C18") (pin "1") (pinfunction "1_1") (pintype "passive"))
      (node (ref "C19") (pin "1") (pinfunction "1_1") (pintype "passive"))
      (node (ref "C2") (pin "2") (pinfunction "2_2") (pintype "passive"))
      (node (ref "C20") (pin "1") (pinfunction "1_1") (pintype "passive"))
      (node (ref "C21") (pin "1") (pinfunction "1_1") (pintype "passive"))
      (node (ref "C22") (pin "1") (pinfunction "1_1") (pintype "passive"))
      (node (ref "C23") (pin "1") (pinfunction "1_1") (pintype "passive"))
      (node (ref "C24") (pin "1") (pinfunction "1_1") (pintype "passive"))
      (node (ref "C25") (pin "1") (pinfunction "1_1") (pintype "passive"))
      (node (ref "C26") (pin "1") (pinfunction "1_1") (pintype "passive"))
      (node (ref "C3") (pin "1") (pinfunction "1_1") (pintype "passive"))
      (node (ref "C6") (pin "1") (pinfunction "1_1") (pintype "passive"))
      (node (ref "C7") (pin "1") (pinfunction "1_1") (pintype "passive"))
      (node (ref "C8") (pin "2") (pinfunction "2_2") (pintype "passive"))
      (node (ref "C9") (pin "2") (pinfunction "2_2") (pintype "passive"))
      (node (ref "D1") (pin "1") (pinfunction "1_1") (pintype "passive"))
      (node (ref "D4") (pin "K") (pinfunction "K_K") (pintype "passive"))
      (node (ref "D5") (pin "K") (pinfunction "K_K") (pintype "passive"))
      (node (ref "D6") (pin "K") (pinfunction "K_K") (pintype "passive"))
      (node (ref "IC1") (pin "15") (pinfunction "GND_15") (pintype "passive"))
      (node (ref "IC2") (pin "25") (pinfunction "VSS_25") (pintype "passive"))
      (node (ref "IC3") (pin "1") (pinfunction "GND_1") (pintype "passive"))
      (node (ref "J1") (pin "31") (pinfunction "31_31") (pintype "passive"))
      (node (ref "J1") (pin "32") (pinfunction "32_32") (pintype "passive"))
      (node (ref "J10") (pin "1") (pinfunction "1_1") (pintype "passive"))
      (node (ref "J11") (pin "1") (pinfunction "1_1") (pintype "passive"))
      (node (ref "J16") (pin "3") (pinfunction "3_3") (pintype "passive"))
      (node (ref "J17") (pin "3") (pinfunction "3_3") (pintype "passive"))
      (node (ref "J18") (pin "3") (pinfunction "3_3") (pintype "passive"))
      (node (ref "J19") (pin "3") (pinfunction "3_3") (pintype "passive"))
      (node (ref "J2") (pin "30") (pinfunction "30_30") (pintype "passive"))
      (node (ref "J2") (pin "31") (pinfunction "31_31") (pintype "passive"))
      (node (ref "J3") (pin "1") (pinfunction "1_1") (pintype "passive"))
      (node (ref "J4") (pin "1") (pinfunction "1_1") (pintype "passive"))
      (node (ref "J5") (pin "1") (pinfunction "1_1") (pintype "passive"))
      (node (ref "J6") (pin "1") (pinfunction "1_1") (pintype "passive"))
      (node (ref "J7") (pin "1") (pinfunction "1_1") (pintype "passive"))
      (node (ref "J8") (pin "5") (pinfunction "5_5") (pintype "passive"))
      (node (ref "J9") (pin "1") (pinfunction "1_1") (pintype "passive"))
      (node (ref "P3") (pin "1") (pinfunction "1_1") (pintype "passive"))
      (node (ref "P3") (pin "2") (pinfunction "2_2") (pintype "passive"))
      (node (ref "P3") (pin "3") (pinfunction "3_3") (pintype "passive"))
      (node (ref "P3") (pin "4") (pinfunction "4_4") (pintype "passive"))
      (node (ref "P4") (pin "1") (pinfunction "1_1") (pintype "passive"))
      (node (ref "P4") (pin "2") (pinfunction "2_2") (pintype "passive"))
      (node (ref "P4") (pin "3") (pinfunction "3_3") (pintype "passive"))
      (node (ref "P4") (pin "4") (pinfunction "4_4") (pintype "passive"))
      (node (ref "Q1") (pin "2") (pinfunction "E_2") (pintype "passive"))
      (node (ref "R20") (pin "1") (pinfunction "1_1") (pintype "passive"))
      (node (ref "R21") (pin "1") (pinfunction "1_1") (pintype "passive"))
      (node (ref "R23") (pin "2") (pinfunction "2_2") (pintype "passive"))
      (node (ref "R24") (pin "2") (pinfunction "2_2") (pintype "passive"))
      (node (ref "R4") (pin "1") (pinfunction "1_1") (pintype "passive"))
      (node (ref "R5") (pin "1") (pinfunction "1_1") (pintype "passive"))
      (node (ref "RJ1") (pin "7") (pinfunction "NC_7") (pintype "passive"))
      (node (ref "RJ1") (pin "8") (pinfunction "NC_8") (pintype "passive"))
      (node (ref "RJ1") (pin "MH1") (pinfunction "MH1_MH1") (pintype "passive"))
      (node (ref "RJ1") (pin "MH2") (pinfunction "MH2_MH2") (pintype "passive"))
      (node (ref "RJ1") (pin "MH3") (pinfunction "MH3_MH3") (pintype "passive"))
      (node (ref "RJ1") (pin "MH4") (pinfunction "MH4_MH4") (pintype "passive"))
      (node (ref "SW1") (pin "2") (pinfunction "2_2") (pintype "passive"))
      (node (ref "SW2") (pin "2") (pinfunction "2_2") (pintype "passive"))
      (node (ref "U1") (pin "8") (pinfunction "GND_8") (pintype "passive"))
      (node (ref "U2") (pin "2") (pinfunction "GND_2") (pintype "passive"))
      (node (ref "U2") (pin "8") (pinfunction "RS_8") (pintype "passive"))
      (node (ref "U3") (pin "2") (pinfunction "GND_2") (pintype "passive"))
      (node (ref "U3") (pin "8") (pinfunction "RS_8") (pintype "passive"))
      (node (ref "X1") (pin "2") (pinfunction "GND_2") (pintype "passive"))
    )
    (net (code "126") (name "Net-(BUZZER1--)") (class "Default")
      (node (ref "BUZZER1") (pin "2") (pinfunction "-_2") (pintype "passive"))
      (node (ref "Q1") (pin "3") (pinfunction "C_3") (pintype "passive"))
    )
    (net (code "127") (name "Net-(C8-Pad1)") (class "Default")
      (node (ref "C8") (pin "1") (pinfunction "1_1") (pintype "passive"))
      (node (ref "R6") (pin "2") (pinfunction "2_2") (pintype "passive"))
      (node (ref "R8") (pin "1") (pinfunction "1_1") (pintype "passive"))
    )
    (net (code "128") (name "Net-(C9-Pad1)") (class "Default")
      (node (ref "C9") (pin "1") (pinfunction "1_1") (pintype "passive"))
      (node (ref "R7") (pin "1") (pinfunction "1_1") (pintype "passive"))
      (node (ref "R9") (pin "2") (pinfunction "2_2") (pintype "passive"))
    )
    (net (code "129") (name "Net-(C11-Pad1)") (class "Default")
      (node (ref "C11") (pin "1") (pinfunction "1_1") (pintype "passive"))
      (node (ref "R10") (pin "2") (pinfunction "2_2") (pintype "passive"))
      (node (ref "R12") (pin "1") (pinfunction "1_1") (pintype "passive"))
    )
    (net (code "130") (name "Net-(C12-Pad1)") (class "Default")
      (node (ref "C12") (pin "1") (pinfunction "1_1") (pintype "passive"))
      (node (ref "R11") (pin "1") (pinfunction "1_1") (pintype "passive"))
      (node (ref "R13") (pin "2") (pinfunction "2_2") (pintype "passive"))
    )
    (net (code "131") (name "Net-(D1-Pad2)") (class "Default")
      (node (ref "D1") (pin "2") (pinfunction "2_2") (pintype "passive"))
      (node (ref "J8") (pin "MH1") (pinfunction "MH1_MH1") (pintype "passive"))
      (node (ref "J8") (pin "MH2") (pinfunction "MH2_MH2") (pintype "passive"))
      (node (ref "R4") (pin "2") (pinfunction "2_2") (pintype "passive"))
    )
    (net (code "132") (name "Net-(D4-PadA)") (class "Default")
      (node (ref "D4") (pin "A") (pinfunction "A_A") (pintype "passive"))
      (node (ref "R19") (pin "1") (pinfunction "1_1") (pintype "passive"))
    )
    (net (code "133") (name "Net-(D5-PadA)") (class "Default")
      (node (ref "D5") (pin "A") (pinfunction "A_A") (pintype "passive"))
      (node (ref "R22") (pin "1") (pinfunction "1_1") (pintype "passive"))
    )
    (net (code "134") (name "Net-(D6-PadA)") (class "Default")
      (node (ref "D6") (pin "A") (pinfunction "A_A") (pintype "passive"))
      (node (ref "R25") (pin "1") (pinfunction "1_1") (pintype "passive"))
    )
    (net (code "135") (name "Net-(IC1-C1+)") (class "Default")
      (node (ref "C4") (pin "2") (pinfunction "2_2") (pintype "passive"))
      (node (ref "IC1") (pin "1") (pinfunction "C1+_1") (pintype "passive"))
    )
    (net (code "136") (name "Net-(IC1-C1-)") (class "Default")
      (node (ref "C4") (pin "1") (pinfunction "1_1") (pintype "passive"))
      (node (ref "IC1") (pin "3") (pinfunction "C1-_3") (pintype "passive"))
    )
    (net (code "137") (name "Net-(IC1-C2+)") (class "Default")
      (node (ref "C5") (pin "2") (pinfunction "2_2") (pintype "passive"))
      (node (ref "IC1") (pin "4") (pinfunction "C2+_4") (pintype "passive"))
    )
    (net (code "138") (name "Net-(IC1-C2-)") (class "Default")
      (node (ref "C5") (pin "1") (pinfunction "1_1") (pintype "passive"))
      (node (ref "IC1") (pin "5") (pinfunction "C2-_5") (pintype "passive"))
    )
    (net (code "139") (name "Net-(IC1-V+)") (class "Default")
      (node (ref "C6") (pin "2") (pinfunction "2_2") (pintype "passive"))
      (node (ref "IC1") (pin "2") (pinfunction "V+_2") (pintype "passive"))
    )
    (net (code "140") (name "Net-(IC1-V-)") (class "Default")
      (node (ref "C7") (pin "2") (pinfunction "2_2") (pintype "passive"))
      (node (ref "IC1") (pin "6") (pinfunction "V-_6") (pintype "passive"))
    )
    (net (code "141") (name "Net-(IC2-MDIO)") (class "Default")
      (node (ref "IC2") (pin "12") (pinfunction "MDIO_12") (pintype "passive"))
      (node (ref "R18") (pin "1") (pinfunction "1_1") (pintype "passive"))
    )
    (net (code "142") (name "Net-(IC2-RBIAS)") (class "Default")
      (node (ref "IC2") (pin "24") (pinfunction "RBIAS_24") (pintype "passive"))
      (node (ref "R24") (pin "1") (pinfunction "1_1") (pintype "passive"))
    )
    (net (code "143") (name "Net-(IC2-XTAL1{slash}CLKIN)") (class "Default")
      (node (ref "IC2") (pin "5") (pinfunction "XTAL1/CLKIN_5") (pintype "passive"))
      (node (ref "X1") (pin "3") (pinfunction "OSC2_3") (pintype "passive"))
    )
    (net (code "144") (name "Net-(IC2-XTAL2)") (class "Default")
      (node (ref "IC2") (pin "4") (pinfunction "XTAL2_4") (pintype "passive"))
      (node (ref "X1") (pin "1") (pinfunction "OSC1_1") (pintype "passive"))
    )
    (net (code "145") (name "Net-(Q1-B)") (class "Default")
      (node (ref "Q1") (pin "1") (pinfunction "B_1") (pintype "passive"))
      (node (ref "R3") (pin "2") (pinfunction "2_2") (pintype "passive"))
      (node (ref "R5") (pin "2") (pinfunction "2_2") (pintype "passive"))
    )
    (net (code "146") (name "Net-(RJ1-LED(Y)_A)") (class "Default")
      (node (ref "R20") (pin "2") (pinfunction "2_2") (pintype "passive"))
      (node (ref "RJ1") (pin "12") (pinfunction "LED(Y)_A_12") (pintype "passive"))
    )
    (net (code "147") (name "Net-(RJ1-LED(Y)_K)") (class "Default")
      (node (ref "R21") (pin "2") (pinfunction "2_2") (pintype "passive"))
      (node (ref "RJ1") (pin "11") (pinfunction "LED(Y)_K_11") (pintype "passive"))
    )
    (net (code "148") (name "VCC_3V3") (class "Default")
      (node (ref "IC2") (pin "9") (pinfunction "VDDIO_9") (pintype "passive"))
      (node (ref "J1") (pin "3") (pinfunction "3_3") (pintype "passive"))
      (node (ref "J1") (pin "4") (pinfunction "4_4") (pintype "passive"))
    )
    (net (code "149") (name "VCC_3V3E") (class "Default")
      (node (ref "C24") (pin "2") (pinfunction "2_2") (pintype "passive"))
      (node (ref "C25") (pin "2") (pinfunction "2_2") (pintype "passive"))
      (node (ref "C26") (pin "2") (pinfunction "2_2") (pintype "passive"))
      (node (ref "IC2") (pin "1") (pinfunction "VDD2A_1") (pintype "passive"))
      (node (ref "IC2") (pin "19") (pinfunction "VDD1A_19") (pintype "passive"))
      (node (ref "IC3") (pin "2") (pinfunction "VOUT_2") (pintype "passive"))
      (node (ref "R14") (pin "2") (pinfunction "2_2") (pintype "passive"))
      (node (ref "R15") (pin "2") (pinfunction "2_2") (pintype "passive"))
      (node (ref "R16") (pin "2") (pinfunction "2_2") (pintype "passive"))
      (node (ref "R17") (pin "2") (pinfunction "2_2") (pintype "passive"))
      (node (ref "RJ1") (pin "4") (pinfunction "TCT_4") (pintype "passive"))
      (node (ref "RJ1") (pin "5") (pinfunction "RCT_5") (pintype "passive"))
    )
    (net (code "150") (name "VCC_5V") (class "Default")
      (node (ref "C1") (pin "1") (pinfunction "1_1") (pintype "passive"))
      (node (ref "C10") (pin "2") (pinfunction "2_2") (pintype "passive"))
      (node (ref "C13") (pin "2") (pinfunction "2_2") (pintype "passive"))
      (node (ref "C15") (pin "2") (pinfunction "2_2") (pintype "passive"))
      (node (ref "C16") (pin "2") (pinfunction "2_2") (pintype "passive"))
      (node (ref "C18") (pin "2") (pinfunction "2_2") (pintype "passive"))
      (node (ref "C19") (pin "2") (pinfunction "2_2") (pintype "passive"))
      (node (ref "C2") (pin "1") (pinfunction "1_1") (pintype "passive"))
      (node (ref "C3") (pin "2") (pinfunction "2_2") (pintype "passive"))
      (node (ref "IC1") (pin "16") (pinfunction "VCC_16") (pintype "passive"))
      (node (ref "IC3") (pin "3") (pinfunction "VIN_3") (pintype "passive"))
      (node (ref "J1") (pin "1") (pinfunction "1_1") (pintype "passive"))
      (node (ref "J1") (pin "2") (pinfunction "2_2") (pintype "passive"))
      (node (ref "J10") (pin "4") (pinfunction "4_4") (pintype "passive"))
      (node (ref "J11") (pin "4") (pinfunction "4_4") (pintype "passive"))
      (node (ref "J3") (pin "4") (pinfunction "4_4") (pintype "passive"))
      (node (ref "J4") (pin "4") (pinfunction "4_4") (pintype "passive"))
      (node (ref "J5") (pin "4") (pinfunction "4_4") (pintype "passive"))
      (node (ref "J6") (pin "4") (pinfunction "4_4") (pintype "passive"))
      (node (ref "J7") (pin "4") (pinfunction "4_4") (pintype "passive"))
      (node (ref "J9") (pin "4") (pinfunction "4_4") (pintype "passive"))
      (node (ref "P2") (pin "1") (pinfunction "1_1") (pintype "passive"))
      (node (ref "P2") (pin "2") (pinfunction "2_2") (pintype "passive"))
      (node (ref "P2") (pin "3") (pinfunction "3_3") (pintype "passive"))
      (node (ref "P2") (pin "4") (pinfunction "4_4") (pintype "passive"))
      (node (ref "R1") (pin "2") (pinfunction "2_2") (pintype "passive"))
      (node (ref "R2") (pin "2") (pinfunction "2_2") (pintype "passive"))
      (node (ref "U1") (pin "1") (pinfunction "VCC_1") (pintype "passive"))
      (node (ref "U2") (pin "3") (pinfunction "VCC_3") (pintype "passive"))
      (node (ref "U3") (pin "3") (pinfunction "VCC_3") (pintype "passive"))
    )
    (net (code "151") (name "VCC_12V") (class "Default")
      (node (ref "BUZZER1") (pin "1") (pinfunction "+_1") (pintype "passive"))
      (node (ref "J16") (pin "1") (pinfunction "1_1") (pintype "passive"))
      (node (ref "J17") (pin "1") (pinfunction "1_1") (pintype "passive"))
      (node (ref "J18") (pin "1") (pinfunction "1_1") (pintype "passive"))
      (node (ref "J19") (pin "1") (pinfunction "1_1") (pintype "passive"))
      (node (ref "P1") (pin "1") (pinfunction "1_1") (pintype "passive"))
      (node (ref "P1") (pin "2") (pinfunction "2_2") (pintype "passive"))
      (node (ref "P1") (pin "3") (pinfunction "3_3") (pintype "passive"))
      (node (ref "P1") (pin "4") (pinfunction "4_4") (pintype "passive"))
    )
    (net (code "152") (name "unconnected-(IC1-R1IN-Pad13)") (class "Default")
      (node (ref "IC1") (pin "13") (pinfunction "R1IN_13") (pintype "passive+no_connect"))
    )
    (net (code "153") (name "unconnected-(IC1-R1OUT-Pad12)") (class "Default")
      (node (ref "IC1") (pin "12") (pinfunction "R1OUT_12") (pintype "passive+no_connect"))
    )
    (net (code "154") (name "unconnected-(IC1-T1IN-Pad11)") (class "Default")
      (node (ref "IC1") (pin "11") (pinfunction "T1IN_11") (pintype "passive+no_connect"))
    )
    (net (code "155") (name "unconnected-(IC1-T1OUT-Pad14)") (class "Default")
      (node (ref "IC1") (pin "14") (pinfunction "T1OUT_14") (pintype "passive+no_connect"))
    )
    (net (code "156") (name "unconnected-(IC2-RXER{slash}~{PHYAD0}-Pad10)") (class "Default")
      (node (ref "IC2") (pin "10") (pinfunction "RXER/~{PHYAD0}_10") (pintype "passive+no_connect"))
    )
    (net (code "157") (name "unconnected-(IC2-VDDCR-Pad6)") (class "Default")
      (node (ref "IC2") (pin "6") (pinfunction "VDDCR_6") (pintype "passive+no_connect"))
    )
    (net (code "158") (name "unconnected-(J8-Pad1)") (class "Default")
      (node (ref "J8") (pin "1") (pinfunction "1_1") (pintype "passive+no_connect"))
    )
    (net (code "159") (name "unconnected-(J8-Pad4)") (class "Default")
      (node (ref "J8") (pin "4") (pinfunction "4_4") (pintype "passive+no_connect"))
    )
    (net (code "160") (name "unconnected-(J8-Pad6)") (class "Default")
      (node (ref "J8") (pin "6") (pinfunction "6_6") (pintype "passive+no_connect"))
    )
    (net (code "161") (name "unconnected-(J8-Pad7)") (class "Default")
      (node (ref "J8") (pin "7") (pinfunction "7_7") (pintype "passive+no_connect"))
    )
    (net (code "162") (name "unconnected-(J8-Pad8)") (class "Default")
      (node (ref "J8") (pin "8") (pinfunction "8_8") (pintype "passive+no_connect"))
    )
    (net (code "163") (name "unconnected-(J8-Pad9)") (class "Default")
      (node (ref "J8") (pin "9") (pinfunction "9_9") (pintype "passive+no_connect"))
    )
    (net (code "164") (name "unconnected-(U1-D0-Pad2)") (class "Default")
      (node (ref "U1") (pin "2") (pinfunction "D0_2") (pintype "passive+no_connect"))
    )
    (net (code "165") (name "unconnected-(U1-D1-Pad3)") (class "Default")
      (node (ref "U1") (pin "3") (pinfunction "D1_3") (pintype "passive+no_connect"))
    )
    (net (code "166") (name "unconnected-(U1-D2-Pad4)") (class "Default")
      (node (ref "U1") (pin "4") (pinfunction "D2_4") (pintype "passive+no_connect"))
    )
    (net (code "167") (name "unconnected-(U1-D3-Pad5)") (class "Default")
      (node (ref "U1") (pin "5") (pinfunction "D3_5") (pintype "passive+no_connect"))
    )
    (net (code "168") (name "unconnected-(U1-D4-Pad6)") (class "Default")
      (node (ref "U1") (pin "6") (pinfunction "D4_6") (pintype "passive+no_connect"))
    )
    (net (code "169") (name "unconnected-(U1-D5-Pad7)") (class "Default")
      (node (ref "U1") (pin "7") (pinfunction "D5_7") (pintype "passive+no_connect"))
    )
    (net (code "170") (name "unconnected-(U1-RX-Pad13)") (class "Default")
      (node (ref "U1") (pin "13") (pinfunction "RX_13") (pintype "passive+no_connect"))
    )
    (net (code "171") (name "unconnected-(U1-SWCLK-Pad9)") (class "Default")
      (node (ref "U1") (pin "9") (pinfunction "SWCLK_9") (pintype "passive+no_connect"))
    )
    (net (code "172") (name "unconnected-(U1-SWDIO-Pad10)") (class "Default")
      (node (ref "U1") (pin "10") (pinfunction "SWDIO_10") (pintype "passive+no_connect"))
    )
    (net (code "173") (name "unconnected-(U1-TX-Pad14)") (class "Default")
      (node (ref "U1") (pin "14") (pinfunction "TX_14") (pintype "passive+no_connect"))
    )
    (net (code "174") (name "unconnected-(U2-Vref-Pad5)") (class "Default")
      (node (ref "U2") (pin "5") (pinfunction "Vref_5") (pintype "passive+no_connect"))
    )
    (net (code "175") (name "unconnected-(U3-Vref-Pad5)") (class "Default")
      (node (ref "U3") (pin "5") (pinfunction "Vref_5") (pintype "passive+no_connect"))
    )
  )
)
